# Step_down_converter.net
KiCad netlist of a schematic drawn in Altium Designer
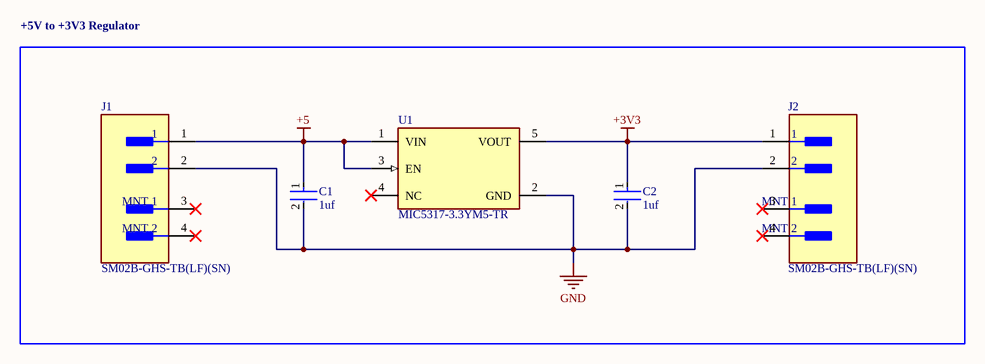
[diagram p0: Step_down_converter.SchDoc]

(export (version "E")
  (design (tool "Eeschema 10.0.6"))
  (components
    (comp (ref "C1")
      (value "1uf")
      (footprint "FP-CC0805-0_85-MFG")
      (description "CAP CER 1UF 10V X7R 0805")
      (fields
        (field (name "MANUFACTURER") "Yageo")
        (field (name "OCTOPART") "https://octopart.com/cc0805kkx7r6bb105-yageo-42522859")
      )
      (libsource (lib "Altium Content Vault") (part "11868f565c42a9108669ba33697ecf6"))
    )
    (comp (ref "C2")
      (value "1uf")
      (footprint "FP-CC0805-0_85-MFG")
      (description "CAP CER 1UF 10V X7R 0805")
      (fields
        (field (name "MANUFACTURER") "Yageo")
        (field (name "OCTOPART") "https://octopart.com/cc0805kkx7r6bb105-yageo-42522859")
      )
      (libsource (lib "Altium Content Vault") (part "11868f565c42a9108669ba33697ecf6"))
    )
    (comp (ref "J1")
      (value "SM02B-GHS-TB(LF)(SN)")
      (footprint "FP-SM02B-GHS-TB_LF_SN-MFG")
      (description "CONN HEADER SMD R/A 2POS 1.25MM")
      (libsource (lib "Altium Content Vault") (part "56ec3178a87b3978bdc1b3682cd516a"))
    )
    (comp (ref "J2")
      (value "SM02B-GHS-TB(LF)(SN)")
      (footprint "FP-SM02B-GHS-TB_LF_SN-MFG")
      (description "CONN HEADER SMD R/A 2POS 1.25MM")
      (libsource (lib "") (part "56ec3178a87b3978bdc1b3682cd516a_1"))
    )
    (comp (ref "U1")
      (value "MIC5317-3.3YM5-TR")
      (footprint "FP-SOT23-5LD-PL-1-MFG")
      (description "IC REG LINEAR 3.3V 150MA SOT23-5")
      (libsource (lib "Altium Content Vault") (part "0a093dae7315cdc977fd108dde87457"))
    )
  )
  (nets
    (net (code "1") (name "+3V3") (class "Default")
      (node (ref "C2") (pin "1") (pinfunction "1_1") (pintype "passive"))
      (node (ref "J2") (pin "1") (pinfunction "1_1") (pintype "passive"))
      (node (ref "U1") (pin "5") (pinfunction "VOUT_5") (pintype "power_in"))
    )
    (net (code "2") (name "+5") (class "Default")
      (node (ref "C1") (pin "1") (pinfunction "1_1") (pintype "passive"))
      (node (ref "J1") (pin "1") (pinfunction "1_1") (pintype "passive"))
      (node (ref "U1") (pin "1") (pinfunction "VIN_1") (pintype "power_in"))
      (node (ref "U1") (pin "3") (pinfunction "EN_3") (pintype "input"))
    )
    (net (code "3") (name "GND") (class "Default")
      (node (ref "C1") (pin "2") (pinfunction "2_2") (pintype "passive"))
      (node (ref "C2") (pin "2") (pinfunction "2_2") (pintype "passive"))
      (node (ref "J1") (pin "2") (pinfunction "2_2") (pintype "passive"))
      (node (ref "J2") (pin "2") (pinfunction "2_2") (pintype "passive"))
      (node (ref "U1") (pin "2") (pinfunction "GND_2") (pintype "power_in"))
    )
    (net (code "4") (name "unconnected-(J1-MNT_1-Pad3)") (class "Default")
      (node (ref "J1") (pin "3") (pinfunction "MNT_1_3") (pintype "passive+no_connect"))
    )
    (net (code "5") (name "unconnected-(J1-MNT_2-Pad4)") (class "Default")
      (node (ref "J1") (pin "4") (pinfunction "MNT_2_4") (pintype "passive+no_connect"))
    )
    (net (code "6") (name "unconnected-(J2-MNT_1-Pad3)") (class "Default")
      (node (ref "J2") (pin "3") (pinfunction "MNT_1_3") (pintype "passive+no_connect"))
    )
    (net (code "7") (name "unconnected-(J2-MNT_2-Pad4)") (class "Default")
      (node (ref "J2") (pin "4") (pinfunction "MNT_2_4") (pintype "passive+no_connect"))
    )
    (net (code "8") (name "unconnected-(U1-NC-Pad4)") (class "Default")
      (node (ref "U1") (pin "4") (pinfunction "NC_4") (pintype "passive+no_connect"))
    )
  )
)
